# MSP430.net
KiCad netlist of a schematic drawn in Altium Designer
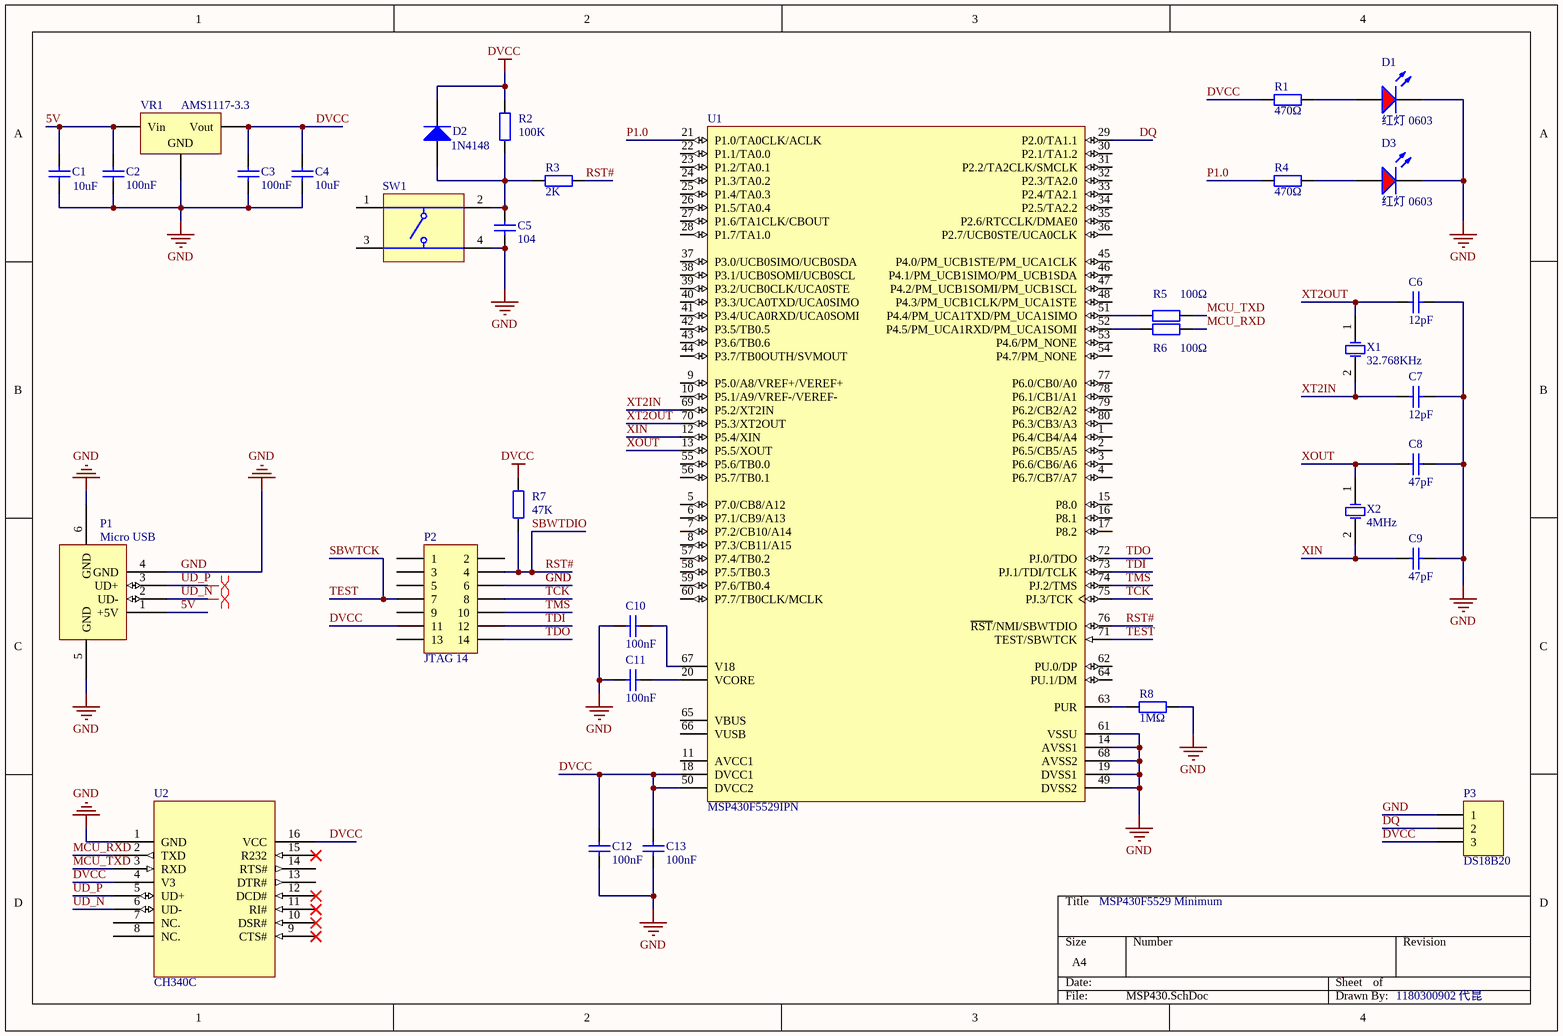
[diagram p0: MSP430.SchDoc]

(export (version "E")
  (design (tool "Eeschema 10.0.6"))
  (components
    (comp (ref "C1")
      (value "10uF")
      (footprint "0603_C")
      (description "贴片电容")
      (libsource (lib "Miscellaneous Devices LC") (part "0603 10uF (106) 10% 10V"))
    )
    (comp (ref "C2")
      (value "100nF")
      (footprint "0603_C")
      (description "贴片电容")
      (libsource (lib "Miscellaneous Devices LC") (part "0603 100nF (104) 10% 50V"))
    )
    (comp (ref "C3")
      (value "100nF")
      (footprint "0603_C")
      (description "贴片电容")
      (libsource (lib "Miscellaneous Devices LC") (part "0603 100nF (104) 10% 50V"))
    )
    (comp (ref "C4")
      (value "10uF")
      (footprint "0603_C")
      (description "贴片电容")
      (libsource (lib "Miscellaneous Devices LC") (part "0603 10uF (106) 10% 10V"))
    )
    (comp (ref "C5")
      (value "104")
      (footprint "0603_C")
      (description "贴片电容")
      (libsource (lib "Miscellaneous Devices LC") (part "0603 1uF (105) 10% 50V"))
    )
    (comp (ref "C6")
      (value "12pF")
      (footprint "0603_C")
      (description "贴片电容")
      (libsource (lib "Miscellaneous Devices LC") (part "0603 12pF (120) 5% 50V"))
    )
    (comp (ref "C7")
      (value "12pF")
      (footprint "0603_C")
      (description "贴片电容")
      (libsource (lib "Miscellaneous Devices LC") (part "0603 12pF (120) 5% 50V"))
    )
    (comp (ref "C8")
      (value "47pF")
      (footprint "0603_C")
      (description "贴片电容")
      (libsource (lib "Miscellaneous Devices LC") (part "0603 47pF (470) 5% 50V"))
    )
    (comp (ref "C9")
      (value "47pF")
      (footprint "0603_C")
      (description "贴片电容")
      (libsource (lib "Miscellaneous Devices LC") (part "0603 47pF (470) 5% 50V"))
    )
    (comp (ref "C10")
      (value "100nF")
      (footprint "0603_C")
      (description "贴片电容")
      (libsource (lib "Miscellaneous Devices LC") (part "0603 100nF (104) 10% 50V"))
    )
    (comp (ref "C11")
      (value "100nF")
      (footprint "0603_C")
      (description "贴片电容")
      (libsource (lib "Miscellaneous Devices LC") (part "0603 100nF (104) 10% 50V"))
    )
    (comp (ref "C12")
      (value "100nF")
      (footprint "0603_C")
      (description "贴片电容")
      (libsource (lib "Miscellaneous Devices LC") (part "0603 100nF (104) 10% 50V"))
    )
    (comp (ref "C13")
      (value "100nF")
      (footprint "0603_C")
      (description "贴片电容")
      (libsource (lib "Miscellaneous Devices LC") (part "0603 100nF (104) 10% 50V"))
    )
    (comp (ref "D1")
      (value "红灯 0603")
      (footprint "0603_LED_S1")
      (description "发光二极管")
      (libsource (lib "Miscellaneous Devices LC") (part "0603 红灯"))
    )
    (comp (ref "D2")
      (value "1N4148")
      (footprint "SOD-323")
      (description "二极管")
      (libsource (lib "Miscellaneous Devices LC") (part "SOD-323 1N4148WS T4"))
    )
    (comp (ref "D3")
      (value "红灯 0603")
      (footprint "0603_LED_S1")
      (description "发光二极管")
      (libsource (lib "Miscellaneous Devices LC") (part "0603 红灯"))
    )
    (comp (ref "P1") (value "Micro USB") (footprint "USBAM") (libsource (lib "CH340C") (part "USB")))
    (comp (ref "P2")
      (value "JTAG 14")
      (footprint "HDR2X7")
      (description "Header, 7-Pin, Dual row")
      (fields (field (name "PUBLISHER") "Altium Limited"))
      (libsource (lib "Miscellaneous Connectors") (part "Header 7X2"))
    )
    (comp (ref "P3")
      (value "DS18B20")
      (footprint "HDR1X3")
      (description "Header, 3-Pin")
      (fields (field (name "PUBLISHER") "Altium Limited"))
      (libsource (lib "Miscellaneous Connectors") (part "Header 3"))
    )
    (comp (ref "R1")
      (value "470Ω")
      (footprint "0603_R")
      (description "贴片电阻")
      (libsource (lib "Miscellaneous Devices LC") (part "0603 470Ω (4700) 1%"))
    )
    (comp (ref "R2")
      (value "100K")
      (footprint "0603_R")
      (description "贴片电阻")
      (libsource (lib "Miscellaneous Devices LC") (part "0603 2.7KΩ (2701) 1%"))
    )
    (comp (ref "R3")
      (value "2K")
      (footprint "0603_R")
      (description "贴片电阻")
      (libsource (lib "Miscellaneous Devices LC") (part "0603 10KΩ (1002) 1%"))
    )
    (comp (ref "R4")
      (value "470Ω")
      (footprint "0603_R")
      (description "贴片电阻")
      (libsource (lib "Miscellaneous Devices LC") (part "0603 470Ω (4700) 1%"))
    )
    (comp (ref "R5")
      (value "100Ω")
      (footprint "0603_R")
      (description "贴片电阻")
      (libsource (lib "Miscellaneous Devices LC") (part "0603 100Ω (1000) 1%"))
    )
    (comp (ref "R6")
      (value "100Ω")
      (footprint "0603_R")
      (description "贴片电阻")
      (libsource (lib "Miscellaneous Devices LC") (part "0603 100Ω (1000) 1%"))
    )
    (comp (ref "R7")
      (value "47K")
      (footprint "0603_R")
      (description "贴片电阻")
      (libsource (lib "Miscellaneous Devices LC") (part "0603 47KΩ (4702) 1%"))
    )
    (comp (ref "R8")
      (value "1MΩ")
      (footprint "0603_R")
      (description "贴片电阻")
      (libsource (lib "Miscellaneous Devices LC") (part "0603 1MΩ (1004) 1%"))
    )
    (comp (ref "SW1")
      (value "1825910-6")
      (footprint "TECO-1825910-6_V")
      (description "Tact Switch, SPST-NO, 0.05 A, -35 to 85 degC, 4-Pin THD, RoHS, Bulk")
      (fields (field (name "MANUFACTURER") "TE Connectivity"))
      (libsource (lib "Altium Content Vault") (part "SW-SPST-4_A"))
    )
    (comp (ref "U1")
      (value "MSP430F5529IPN")
      (footprint "TI-PN80_N")
      (fields (field (name "MANUFACTURER") "Texas Instruments"))
      (libsource (lib "TI Microcontroller MSP430") (part "MSP430F5529IPN"))
    )
    (comp (ref "U2")
      (value "CH340C")
      (footprint "SOP16")
      (description "USB to Serial / UART")
      (libsource (lib "CH340C") (part "CH340C"))
    )
    (comp (ref "VR1")
      (value "AMS1117-3.3")
      (footprint "SOT-223")
      (description "低压差线性稳压(LDO)")
      (libsource (lib "Miscellaneous Devices LC") (part "SOT-223 AMS1117-3.3"))
    )
    (comp (ref "X1")
      (value "32.768KHz")
      (footprint "ABRA-AB15T-2_V")
      (description "晶振")
      (fields (field (name "PARTNUMBER") "AB15T-32.768KHZ") (field (name "MANUFACTURER") "Abracon"))
      (libsource (lib "Altium Content Vault") (part "ABRA-XTAL_1-2-2"))
    )
    (comp (ref "X2")
      (value "4MHz")
      (footprint "ABRA-ABLS-14.7456MHZ-B2-T_V")
      (description "晶振")
      (fields (field (name "MANUFACTURER") "ABRACON") (field (name "TOLERANCE") "30PPM"))
      (libsource (lib "Altium Content Vault") (part "XTAL_1-2-2"))
    )
  )
  (nets
    (net (code "1") (name "/5V") (class "Default")
      (node (ref "C1") (pin "2") (pinfunction "2_2") (pintype "passive"))
      (node (ref "C2") (pin "2") (pinfunction "2_2") (pintype "passive"))
      (node (ref "P1") (pin "1") (pinfunction "+5V_1") (pintype "power_in"))
      (node (ref "VR1") (pin "3") (pinfunction "Vin_3") (pintype "passive"))
    )
    (net (code "2") (name "/DQ") (class "Default")
      (node (ref "P3") (pin "2") (pinfunction "2_2") (pintype "passive"))
      (node (ref "U1") (pin "29") (pinfunction "P2.0/TA1.1_29") (pintype "bidirectional"))
    )
    (net (code "3") (name "/MCU_RXD") (class "Default")
      (node (ref "R6") (pin "2") (pinfunction "2_2") (pintype "passive"))
      (node (ref "U2") (pin "2") (pinfunction "TXD_2") (pintype "output"))
    )
    (net (code "4") (name "/MCU_TXD") (class "Default")
      (node (ref "R5") (pin "2") (pinfunction "2_2") (pintype "passive"))
      (node (ref "U2") (pin "3") (pinfunction "RXD_3") (pintype "input"))
    )
    (net (code "5") (name "/P1.0") (class "Default")
      (node (ref "R4") (pin "1") (pinfunction "1_1") (pintype "passive"))
      (node (ref "U1") (pin "21") (pinfunction "P1.0/TA0CLK/ACLK_21") (pintype "bidirectional"))
    )
    (net (code "6") (name "/RST#") (class "Default")
      (node (ref "P2") (pin "4") (pinfunction "4_4") (pintype "passive"))
      (node (ref "R3") (pin "2") (pinfunction "2_2") (pintype "passive"))
      (node (ref "R7") (pin "1") (pinfunction "1_1") (pintype "passive"))
      (node (ref "U1") (pin "76") (pinfunction "~{RST}/NMI/SBWTDIO_76") (pintype "bidirectional"))
    )
    (net (code "7") (name "/SBWTCK") (class "Default")
      (node (ref "P2") (pin "7") (pinfunction "7_7") (pintype "passive"))
      (node (ref "U1") (pin "71") (pinfunction "TEST/SBWTCK_71") (pintype "input"))
    )
    (net (code "8") (name "/TCK") (class "Default")
      (node (ref "P2") (pin "8") (pinfunction "8_8") (pintype "passive"))
      (node (ref "U1") (pin "75") (pinfunction "PJ.3/TCK_75") (pintype "bidirectional"))
    )
    (net (code "9") (name "/TDI") (class "Default")
      (node (ref "P2") (pin "12") (pinfunction "12_12") (pintype "passive"))
      (node (ref "U1") (pin "73") (pinfunction "PJ.1/TDI/TCLK_73") (pintype "bidirectional"))
    )
    (net (code "10") (name "/TDO") (class "Default")
      (node (ref "P2") (pin "14") (pinfunction "14_14") (pintype "passive"))
      (node (ref "U1") (pin "72") (pinfunction "PJ.0/TDO_72") (pintype "bidirectional"))
    )
    (net (code "11") (name "/TMS") (class "Default")
      (node (ref "P2") (pin "10") (pinfunction "10_10") (pintype "passive"))
      (node (ref "U1") (pin "74") (pinfunction "PJ.2/TMS_74") (pintype "bidirectional"))
    )
    (net (code "12") (name "/UD_N") (class "Default")
      (node (ref "P1") (pin "2") (pinfunction "UD-_2") (pintype "bidirectional"))
      (node (ref "U2") (pin "6") (pinfunction "UD-_6") (pintype "bidirectional"))
    )
    (net (code "13") (name "/UD_P") (class "Default")
      (node (ref "P1") (pin "3") (pinfunction "UD+_3") (pintype "bidirectional"))
      (node (ref "U2") (pin "5") (pinfunction "UD+_5") (pintype "bidirectional"))
    )
    (net (code "14") (name "/XIN") (class "Default")
      (node (ref "C9") (pin "1") (pinfunction "1_1") (pintype "passive"))
      (node (ref "U1") (pin "12") (pinfunction "P5.4/XIN_12") (pintype "bidirectional"))
      (node (ref "X2") (pin "2") (pinfunction "X2_2") (pintype "passive"))
    )
    (net (code "15") (name "/XOUT") (class "Default")
      (node (ref "C8") (pin "1") (pinfunction "1_1") (pintype "passive"))
      (node (ref "U1") (pin "13") (pinfunction "P5.5/XOUT_13") (pintype "bidirectional"))
      (node (ref "X2") (pin "1") (pinfunction "X1_1") (pintype "passive"))
    )
    (net (code "16") (name "/XT2IN") (class "Default")
      (node (ref "C7") (pin "1") (pinfunction "1_1") (pintype "passive"))
      (node (ref "U1") (pin "69") (pinfunction "P5.2/XT2IN_69") (pintype "bidirectional"))
      (node (ref "X1") (pin "2") (pinfunction "X2_2") (pintype "passive"))
    )
    (net (code "17") (name "/XT2OUT") (class "Default")
      (node (ref "C6") (pin "1") (pinfunction "1_1") (pintype "passive"))
      (node (ref "U1") (pin "70") (pinfunction "P5.3/XT2OUT_70") (pintype "bidirectional"))
      (node (ref "X1") (pin "1") (pinfunction "X1_1") (pintype "passive"))
    )
    (net (code "18") (name "DVCC") (class "Default")
      (node (ref "C12") (pin "2") (pinfunction "2_2") (pintype "passive"))
      (node (ref "C13") (pin "2") (pinfunction "2_2") (pintype "passive"))
      (node (ref "C3") (pin "2") (pinfunction "2_2") (pintype "passive"))
      (node (ref "C4") (pin "2") (pinfunction "2_2") (pintype "passive"))
      (node (ref "D2") (pin "2") (pinfunction "K_2") (pintype "passive"))
      (node (ref "P2") (pin "11") (pinfunction "11_11") (pintype "passive"))
      (node (ref "P3") (pin "3") (pinfunction "3_3") (pintype "passive"))
      (node (ref "R1") (pin "1") (pinfunction "1_1") (pintype "passive"))
      (node (ref "R2") (pin "2") (pinfunction "2_2") (pintype "passive"))
      (node (ref "R7") (pin "2") (pinfunction "2_2") (pintype "passive"))
      (node (ref "U1") (pin "18") (pinfunction "DVCC1_18") (pintype "power_in"))
      (node (ref "U1") (pin "50") (pinfunction "DVCC2_50") (pintype "power_in"))
      (node (ref "U2") (pin "16") (pinfunction "VCC_16") (pintype "power_in"))
      (node (ref "U2") (pin "4") (pinfunction "V3_4") (pintype "power_in"))
      (node (ref "VR1") (pin "2") (pinfunction "Vout_2") (pintype "passive"))
    )
    (net (code "19") (name "GND") (class "Default")
      (node (ref "C1") (pin "1") (pinfunction "1_1") (pintype "passive"))
      (node (ref "C10") (pin "1") (pinfunction "1_1") (pintype "passive"))
      (node (ref "C11") (pin "1") (pinfunction "1_1") (pintype "passive"))
      (node (ref "C12") (pin "1") (pinfunction "1_1") (pintype "passive"))
      (node (ref "C13") (pin "1") (pinfunction "1_1") (pintype "passive"))
      (node (ref "C2") (pin "1") (pinfunction "1_1") (pintype "passive"))
      (node (ref "C3") (pin "1") (pinfunction "1_1") (pintype "passive"))
      (node (ref "C4") (pin "1") (pinfunction "1_1") (pintype "passive"))
      (node (ref "C5") (pin "1") (pinfunction "1_1") (pintype "passive"))
      (node (ref "C6") (pin "2") (pinfunction "2_2") (pintype "passive"))
      (node (ref "C7") (pin "2") (pinfunction "2_2") (pintype "passive"))
      (node (ref "C8") (pin "2") (pinfunction "2_2") (pintype "passive"))
      (node (ref "C9") (pin "2") (pinfunction "2_2") (pintype "passive"))
      (node (ref "D1") (pin "K") (pinfunction "K_K") (pintype "passive"))
      (node (ref "D3") (pin "K") (pinfunction "K_K") (pintype "passive"))
      (node (ref "P1") (pin "4") (pinfunction "GND_4") (pintype "power_in"))
      (node (ref "P1") (pin "5") (pinfunction "GND_5") (pintype "power_in"))
      (node (ref "P1") (pin "6") (pinfunction "GND_6") (pintype "power_in"))
      (node (ref "P2") (pin "6") (pinfunction "6_6") (pintype "passive"))
      (node (ref "P3") (pin "1") (pinfunction "1_1") (pintype "passive"))
      (node (ref "R8") (pin "2") (pinfunction "2_2") (pintype "passive"))
      (node (ref "SW1") (pin "4") (pinfunction "4_4") (pintype "passive"))
      (node (ref "U1") (pin "14") (pinfunction "AVSS1_14") (pintype "power_in"))
      (node (ref "U1") (pin "19") (pinfunction "DVSS1_19") (pintype "power_in"))
      (node (ref "U1") (pin "49") (pinfunction "DVSS2_49") (pintype "power_in"))
      (node (ref "U1") (pin "61") (pinfunction "VSSU_61") (pintype "power_in"))
      (node (ref "U1") (pin "68") (pinfunction "AVSS2_68") (pintype "power_in"))
      (node (ref "U2") (pin "1") (pinfunction "GND_1") (pintype "power_in"))
      (node (ref "VR1") (pin "1") (pinfunction "GND_1") (pintype "passive"))
    )
    (net (code "20") (name "Net-(D1-PadA)") (class "Default")
      (node (ref "D1") (pin "A") (pinfunction "A_A") (pintype "passive"))
      (node (ref "R1") (pin "2") (pinfunction "2_2") (pintype "passive"))
    )
    (net (code "21") (name "Net-(D2-A)") (class "Default")
      (node (ref "C5") (pin "2") (pinfunction "2_2") (pintype "passive"))
      (node (ref "D2") (pin "1") (pinfunction "A_1") (pintype "passive"))
      (node (ref "R2") (pin "1") (pinfunction "1_1") (pintype "passive"))
      (node (ref "R3") (pin "1") (pinfunction "1_1") (pintype "passive"))
      (node (ref "SW1") (pin "2") (pinfunction "2_2") (pintype "passive"))
    )
    (net (code "22") (name "Net-(D3-PadA)") (class "Default")
      (node (ref "D3") (pin "A") (pinfunction "A_A") (pintype "passive"))
      (node (ref "R4") (pin "2") (pinfunction "2_2") (pintype "passive"))
    )
    (net (code "23") (name "Net-(U1-P4.4{slash}PM_UCA1TXD{slash}PM_UCA1SIMO)") (class "Default")
      (node (ref "R5") (pin "1") (pinfunction "1_1") (pintype "passive"))
      (node (ref "U1") (pin "51") (pinfunction "P4.4/PM_UCA1TXD/PM_UCA1SIMO_51") (pintype "bidirectional"))
    )
    (net (code "24") (name "Net-(U1-P4.5{slash}PM_UCA1RXD{slash}PM_UCA1SOMI)") (class "Default")
      (node (ref "R6") (pin "1") (pinfunction "1_1") (pintype "passive"))
      (node (ref "U1") (pin "52") (pinfunction "P4.5/PM_UCA1RXD/PM_UCA1SOMI_52") (pintype "bidirectional"))
    )
    (net (code "25") (name "Net-(U1-PUR)") (class "Default")
      (node (ref "R8") (pin "1") (pinfunction "1_1") (pintype "passive"))
      (node (ref "U1") (pin "63") (pinfunction "PUR_63") (pintype "passive"))
    )
    (net (code "26") (name "Net-(U1-V18)") (class "Default")
      (node (ref "C10") (pin "2") (pinfunction "2_2") (pintype "passive"))
      (node (ref "U1") (pin "67") (pinfunction "V18_67") (pintype "passive"))
    )
    (net (code "27") (name "Net-(U1-VCORE)") (class "Default")
      (node (ref "C11") (pin "2") (pinfunction "2_2") (pintype "passive"))
      (node (ref "U1") (pin "20") (pinfunction "VCORE_20") (pintype "passive"))
    )
    (net (code "28") (name "unconnected-(P2-Pad1)") (class "Default")
      (node (ref "P2") (pin "1") (pinfunction "1_1") (pintype "passive"))
    )
    (net (code "29") (name "unconnected-(P2-Pad2)") (class "Default")
      (node (ref "P2") (pin "2") (pinfunction "2_2") (pintype "passive"))
    )
    (net (code "30") (name "unconnected-(P2-Pad3)") (class "Default")
      (node (ref "P2") (pin "3") (pinfunction "3_3") (pintype "passive"))
    )
    (net (code "31") (name "unconnected-(P2-Pad5)") (class "Default")
      (node (ref "P2") (pin "5") (pinfunction "5_5") (pintype "passive"))
    )
    (net (code "32") (name "unconnected-(P2-Pad9)") (class "Default")
      (node (ref "P2") (pin "9") (pinfunction "9_9") (pintype "passive"))
    )
    (net (code "33") (name "unconnected-(P2-Pad13)") (class "Default")
      (node (ref "P2") (pin "13") (pinfunction "13_13") (pintype "passive"))
    )
    (net (code "34") (name "unconnected-(SW1-Pad1)") (class "Default")
      (node (ref "SW1") (pin "1") (pinfunction "1_1") (pintype "passive"))
    )
    (net (code "35") (name "unconnected-(SW1-Pad3)") (class "Default")
      (node (ref "SW1") (pin "3") (pinfunction "3_3") (pintype "passive"))
    )
    (net (code "36") (name "unconnected-(U1-AVCC1-Pad11)") (class "Default")
      (node (ref "U1") (pin "11") (pinfunction "AVCC1_11") (pintype "power_in"))
    )
    (net (code "37") (name "unconnected-(U1-P1.1{slash}TA0.0-Pad22)") (class "Default")
      (node (ref "U1") (pin "22") (pinfunction "P1.1/TA0.0_22") (pintype "bidirectional"))
    )
    (net (code "38") (name "unconnected-(U1-P1.2{slash}TA0.1-Pad23)") (class "Default")
      (node (ref "U1") (pin "23") (pinfunction "P1.2/TA0.1_23") (pintype "bidirectional"))
    )
    (net (code "39") (name "unconnected-(U1-P1.3{slash}TA0.2-Pad24)") (class "Default")
      (node (ref "U1") (pin "24") (pinfunction "P1.3/TA0.2_24") (pintype "bidirectional"))
    )
    (net (code "40") (name "unconnected-(U1-P1.4{slash}TA0.3-Pad25)") (class "Default")
      (node (ref "U1") (pin "25") (pinfunction "P1.4/TA0.3_25") (pintype "bidirectional"))
    )
    (net (code "41") (name "unconnected-(U1-P1.5{slash}TA0.4-Pad26)") (class "Default")
      (node (ref "U1") (pin "26") (pinfunction "P1.5/TA0.4_26") (pintype "bidirectional"))
    )
    (net (code "42") (name "unconnected-(U1-P1.6{slash}TA1CLK{slash}CBOUT-Pad27)") (class "Default")
      (node (ref "U1") (pin "27") (pinfunction "P1.6/TA1CLK/CBOUT_27") (pintype "bidirectional"))
    )
    (net (code "43") (name "unconnected-(U1-P1.7{slash}TA1.0-Pad28)") (class "Default")
      (node (ref "U1") (pin "28") (pinfunction "P1.7/TA1.0_28") (pintype "bidirectional"))
    )
    (net (code "44") (name "unconnected-(U1-P2.1{slash}TA1.2-Pad30)") (class "Default")
      (node (ref "U1") (pin "30") (pinfunction "P2.1/TA1.2_30") (pintype "bidirectional"))
    )
    (net (code "45") (name "unconnected-(U1-P2.2{slash}TA2CLK{slash}SMCLK-Pad31)") (class "Default")
      (node (ref "U1") (pin "31") (pinfunction "P2.2/TA2CLK/SMCLK_31") (pintype "bidirectional"))
    )
    (net (code "46") (name "unconnected-(U1-P2.3{slash}TA2.0-Pad32)") (class "Default")
      (node (ref "U1") (pin "32") (pinfunction "P2.3/TA2.0_32") (pintype "bidirectional"))
    )
    (net (code "47") (name "unconnected-(U1-P2.4{slash}TA2.1-Pad33)") (class "Default")
      (node (ref "U1") (pin "33") (pinfunction "P2.4/TA2.1_33") (pintype "bidirectional"))
    )
    (net (code "48") (name "unconnected-(U1-P2.5{slash}TA2.2-Pad34)") (class "Default")
      (node (ref "U1") (pin "34") (pinfunction "P2.5/TA2.2_34") (pintype "bidirectional"))
    )
    (net (code "49") (name "unconnected-(U1-P2.6{slash}RTCCLK{slash}DMAE0-Pad35)") (class "Default")
      (node (ref "U1") (pin "35") (pinfunction "P2.6/RTCCLK/DMAE0_35") (pintype "bidirectional"))
    )
    (net (code "50") (name "unconnected-(U1-P2.7{slash}UCB0STE{slash}UCA0CLK-Pad36)") (class "Default")
      (node (ref "U1") (pin "36") (pinfunction "P2.7/UCB0STE/UCA0CLK_36") (pintype "bidirectional"))
    )
    (net (code "51") (name "unconnected-(U1-P3.0{slash}UCB0SIMO{slash}UCB0SDA-Pad37)") (class "Default")
      (node (ref "U1") (pin "37") (pinfunction "P3.0/UCB0SIMO/UCB0SDA_37") (pintype "bidirectional"))
    )
    (net (code "52") (name "unconnected-(U1-P3.1{slash}UCB0SOMI{slash}UCB0SCL-Pad38)") (class "Default")
      (node (ref "U1") (pin "38") (pinfunction "P3.1/UCB0SOMI/UCB0SCL_38") (pintype "bidirectional"))
    )
    (net (code "53") (name "unconnected-(U1-P3.2{slash}UCB0CLK{slash}UCA0STE-Pad39)") (class "Default")
      (node (ref "U1") (pin "39") (pinfunction "P3.2/UCB0CLK/UCA0STE_39") (pintype "bidirectional"))
    )
    (net (code "54") (name "unconnected-(U1-P3.3{slash}UCA0TXD{slash}UCA0SIMO-Pad40)") (class "Default")
      (node (ref "U1") (pin "40") (pinfunction "P3.3/UCA0TXD/UCA0SIMO_40") (pintype "bidirectional"))
    )
    (net (code "55") (name "unconnected-(U1-P3.4{slash}UCA0RXD{slash}UCA0SOMI-Pad41)") (class "Default")
      (node (ref "U1") (pin "41") (pinfunction "P3.4/UCA0RXD/UCA0SOMI_41") (pintype "bidirectional"))
    )
    (net (code "56") (name "unconnected-(U1-P3.5{slash}TB0.5-Pad42)") (class "Default")
      (node (ref "U1") (pin "42") (pinfunction "P3.5/TB0.5_42") (pintype "bidirectional"))
    )
    (net (code "57") (name "unconnected-(U1-P3.6{slash}TB0.6-Pad43)") (class "Default")
      (node (ref "U1") (pin "43") (pinfunction "P3.6/TB0.6_43") (pintype "bidirectional"))
    )
    (net (code "58") (name "unconnected-(U1-P3.7{slash}TB0OUTH{slash}SVMOUT-Pad44)") (class "Default")
      (node (ref "U1") (pin "44") (pinfunction "P3.7/TB0OUTH/SVMOUT_44") (pintype "bidirectional"))
    )
    (net (code "59") (name "unconnected-(U1-P4.0{slash}PM_UCB1STE{slash}PM_UCA1CLK-Pad45)") (class "Default")
      (node (ref "U1") (pin "45") (pinfunction "P4.0/PM_UCB1STE/PM_UCA1CLK_45") (pintype "bidirectional"))
    )
    (net (code "60") (name "unconnected-(U1-P4.1{slash}PM_UCB1SIMO{slash}PM_UCB1SDA-Pad46)") (class "Default")
      (node (ref "U1") (pin "46") (pinfunction "P4.1/PM_UCB1SIMO/PM_UCB1SDA_46") (pintype "bidirectional"))
    )
    (net (code "61") (name "unconnected-(U1-P4.2{slash}PM_UCB1SOMI{slash}PM_UCB1SCL-Pad47)") (class "Default")
      (node (ref "U1") (pin "47") (pinfunction "P4.2/PM_UCB1SOMI/PM_UCB1SCL_47") (pintype "bidirectional"))
    )
    (net (code "62") (name "unconnected-(U1-P4.3{slash}PM_UCB1CLK{slash}PM_UCA1STE-Pad48)") (class "Default")
      (node (ref "U1") (pin "48") (pinfunction "P4.3/PM_UCB1CLK/PM_UCA1STE_48") (pintype "bidirectional"))
    )
    (net (code "63") (name "unconnected-(U1-P4.6{slash}PM_NONE-Pad53)") (class "Default")
      (node (ref "U1") (pin "53") (pinfunction "P4.6/PM_NONE_53") (pintype "bidirectional"))
    )
    (net (code "64") (name "unconnected-(U1-P4.7{slash}PM_NONE-Pad54)") (class "Default")
      (node (ref "U1") (pin "54") (pinfunction "P4.7/PM_NONE_54") (pintype "bidirectional"))
    )
    (net (code "65") (name "unconnected-(U1-P5.0{slash}A8{slash}VREF+{slash}VEREF+-Pad9)") (class "Default")
      (node (ref "U1") (pin "9") (pinfunction "P5.0/A8/VREF+/VEREF+_9") (pintype "bidirectional"))
    )
    (net (code "66") (name "unconnected-(U1-P5.1{slash}A9{slash}VREF-{slash}VEREF--Pad10)") (class "Default")
      (node (ref "U1") (pin "10") (pinfunction "P5.1/A9/VREF-/VEREF-_10") (pintype "bidirectional"))
    )
    (net (code "67") (name "unconnected-(U1-P5.6{slash}TB0.0-Pad55)") (class "Default")
      (node (ref "U1") (pin "55") (pinfunction "P5.6/TB0.0_55") (pintype "bidirectional"))
    )
    (net (code "68") (name "unconnected-(U1-P5.7{slash}TB0.1-Pad56)") (class "Default")
      (node (ref "U1") (pin "56") (pinfunction "P5.7/TB0.1_56") (pintype "bidirectional"))
    )
    (net (code "69") (name "unconnected-(U1-P6.0{slash}CB0{slash}A0-Pad77)") (class "Default")
      (node (ref "U1") (pin "77") (pinfunction "P6.0/CB0/A0_77") (pintype "bidirectional"))
    )
    (net (code "70") (name "unconnected-(U1-P6.1{slash}CB1{slash}A1-Pad78)") (class "Default")
      (node (ref "U1") (pin "78") (pinfunction "P6.1/CB1/A1_78") (pintype "bidirectional"))
    )
    (net (code "71") (name "unconnected-(U1-P6.2{slash}CB2{slash}A2-Pad79)") (class "Default")
      (node (ref "U1") (pin "79") (pinfunction "P6.2/CB2/A2_79") (pintype "bidirectional"))
    )
    (net (code "72") (name "unconnected-(U1-P6.3{slash}CB3{slash}A3-Pad80)") (class "Default")
      (node (ref "U1") (pin "80") (pinfunction "P6.3/CB3/A3_80") (pintype "bidirectional"))
    )
    (net (code "73") (name "unconnected-(U1-P6.4{slash}CB4{slash}A4-Pad1)") (class "Default")
      (node (ref "U1") (pin "1") (pinfunction "P6.4/CB4/A4_1") (pintype "bidirectional"))
    )
    (net (code "74") (name "unconnected-(U1-P6.5{slash}CB5{slash}A5-Pad2)") (class "Default")
      (node (ref "U1") (pin "2") (pinfunction "P6.5/CB5/A5_2") (pintype "bidirectional"))
    )
    (net (code "75") (name "unconnected-(U1-P6.6{slash}CB6{slash}A6-Pad3)") (class "Default")
      (node (ref "U1") (pin "3") (pinfunction "P6.6/CB6/A6_3") (pintype "bidirectional"))
    )
    (net (code "76") (name "unconnected-(U1-P6.7{slash}CB7{slash}A7-Pad4)") (class "Default")
      (node (ref "U1") (pin "4") (pinfunction "P6.7/CB7/A7_4") (pintype "bidirectional"))
    )
    (net (code "77") (name "unconnected-(U1-P7.0{slash}CB8{slash}A12-Pad5)") (class "Default")
      (node (ref "U1") (pin "5") (pinfunction "P7.0/CB8/A12_5") (pintype "bidirectional"))
    )
    (net (code "78") (name "unconnected-(U1-P7.1{slash}CB9{slash}A13-Pad6)") (class "Default")
      (node (ref "U1") (pin "6") (pinfunction "P7.1/CB9/A13_6") (pintype "bidirectional"))
    )
    (net (code "79") (name "unconnected-(U1-P7.2{slash}CB10{slash}A14-Pad7)") (class "Default")
      (node (ref "U1") (pin "7") (pinfunction "P7.2/CB10/A14_7") (pintype "bidirectional"))
    )
    (net (code "80") (name "unconnected-(U1-P7.3{slash}CB11{slash}A15-Pad8)") (class "Default")
      (node (ref "U1") (pin "8") (pinfunction "P7.3/CB11/A15_8") (pintype "bidirectional"))
    )
    (net (code "81") (name "unconnected-(U1-P7.4{slash}TB0.2-Pad57)") (class "Default")
      (node (ref "U1") (pin "57") (pinfunction "P7.4/TB0.2_57") (pintype "bidirectional"))
    )
    (net (code "82") (name "unconnected-(U1-P7.5{slash}TB0.3-Pad58)") (class "Default")
      (node (ref "U1") (pin "58") (pinfunction "P7.5/TB0.3_58") (pintype "bidirectional"))
    )
    (net (code "83") (name "unconnected-(U1-P7.6{slash}TB0.4-Pad59)") (class "Default")
      (node (ref "U1") (pin "59") (pinfunction "P7.6/TB0.4_59") (pintype "bidirectional"))
    )
    (net (code "84") (name "unconnected-(U1-P7.7{slash}TB0CLK{slash}MCLK-Pad60)") (class "Default")
      (node (ref "U1") (pin "60") (pinfunction "P7.7/TB0CLK/MCLK_60") (pintype "bidirectional"))
    )
    (net (code "85") (name "unconnected-(U1-P8.0-Pad15)") (class "Default")
      (node (ref "U1") (pin "15") (pinfunction "P8.0_15") (pintype "bidirectional"))
    )
    (net (code "86") (name "unconnected-(U1-P8.1-Pad16)") (class "Default")
      (node (ref "U1") (pin "16") (pinfunction "P8.1_16") (pintype "bidirectional"))
    )
    (net (code "87") (name "unconnected-(U1-P8.2-Pad17)") (class "Default")
      (node (ref "U1") (pin "17") (pinfunction "P8.2_17") (pintype "bidirectional"))
    )
    (net (code "88") (name "unconnected-(U1-PU.0{slash}DP-Pad62)") (class "Default")
      (node (ref "U1") (pin "62") (pinfunction "PU.0/DP_62") (pintype "bidirectional"))
    )
    (net (code "89") (name "unconnected-(U1-PU.1{slash}DM-Pad64)") (class "Default")
      (node (ref "U1") (pin "64") (pinfunction "PU.1/DM_64") (pintype "bidirectional"))
    )
    (net (code "90") (name "unconnected-(U1-VBUS-Pad65)") (class "Default")
      (node (ref "U1") (pin "65") (pinfunction "VBUS_65") (pintype "power_in"))
    )
    (net (code "91") (name "unconnected-(U1-VUSB-Pad66)") (class "Default")
      (node (ref "U1") (pin "66") (pinfunction "VUSB_66") (pintype "power_in"))
    )
    (net (code "92") (name "unconnected-(U2-CTS#-Pad9)") (class "Default")
      (node (ref "U2") (pin "9") (pinfunction "CTS#_9") (pintype "input+no_connect"))
    )
    (net (code "93") (name "unconnected-(U2-DCD#-Pad12)") (class "Default")
      (node (ref "U2") (pin "12") (pinfunction "DCD#_12") (pintype "input+no_connect"))
    )
    (net (code "94") (name "unconnected-(U2-DSR#-Pad10)") (class "Default")
      (node (ref "U2") (pin "10") (pinfunction "DSR#_10") (pintype "input+no_connect"))
    )
    (net (code "95") (name "unconnected-(U2-DTR#-Pad13)") (class "Default")
      (node (ref "U2") (pin "13") (pinfunction "DTR#_13") (pintype "output"))
    )
    (net (code "96") (name "unconnected-(U2-NC.-Pad7)") (class "Default")
      (node (ref "U2") (pin "7") (pinfunction "NC._7") (pintype "passive"))
    )
    (net (code "97") (name "unconnected-(U2-NC.-Pad8)") (class "Default")
      (node (ref "U2") (pin "8") (pinfunction "NC._8") (pintype "passive"))
    )
    (net (code "98") (name "unconnected-(U2-R232-Pad15)") (class "Default")
      (node (ref "U2") (pin "15") (pinfunction "R232_15") (pintype "input+no_connect"))
    )
    (net (code "99") (name "unconnected-(U2-RI#-Pad11)") (class "Default")
      (node (ref "U2") (pin "11") (pinfunction "RI#_11") (pintype "input+no_connect"))
    )
    (net (code "100") (name "unconnected-(U2-RTS#-Pad14)") (class "Default")
      (node (ref "U2") (pin "14") (pinfunction "RTS#_14") (pintype "output"))
    )
  )
)
